# udoo.net
KiCad netlist of a schematic drawn in EAGLE
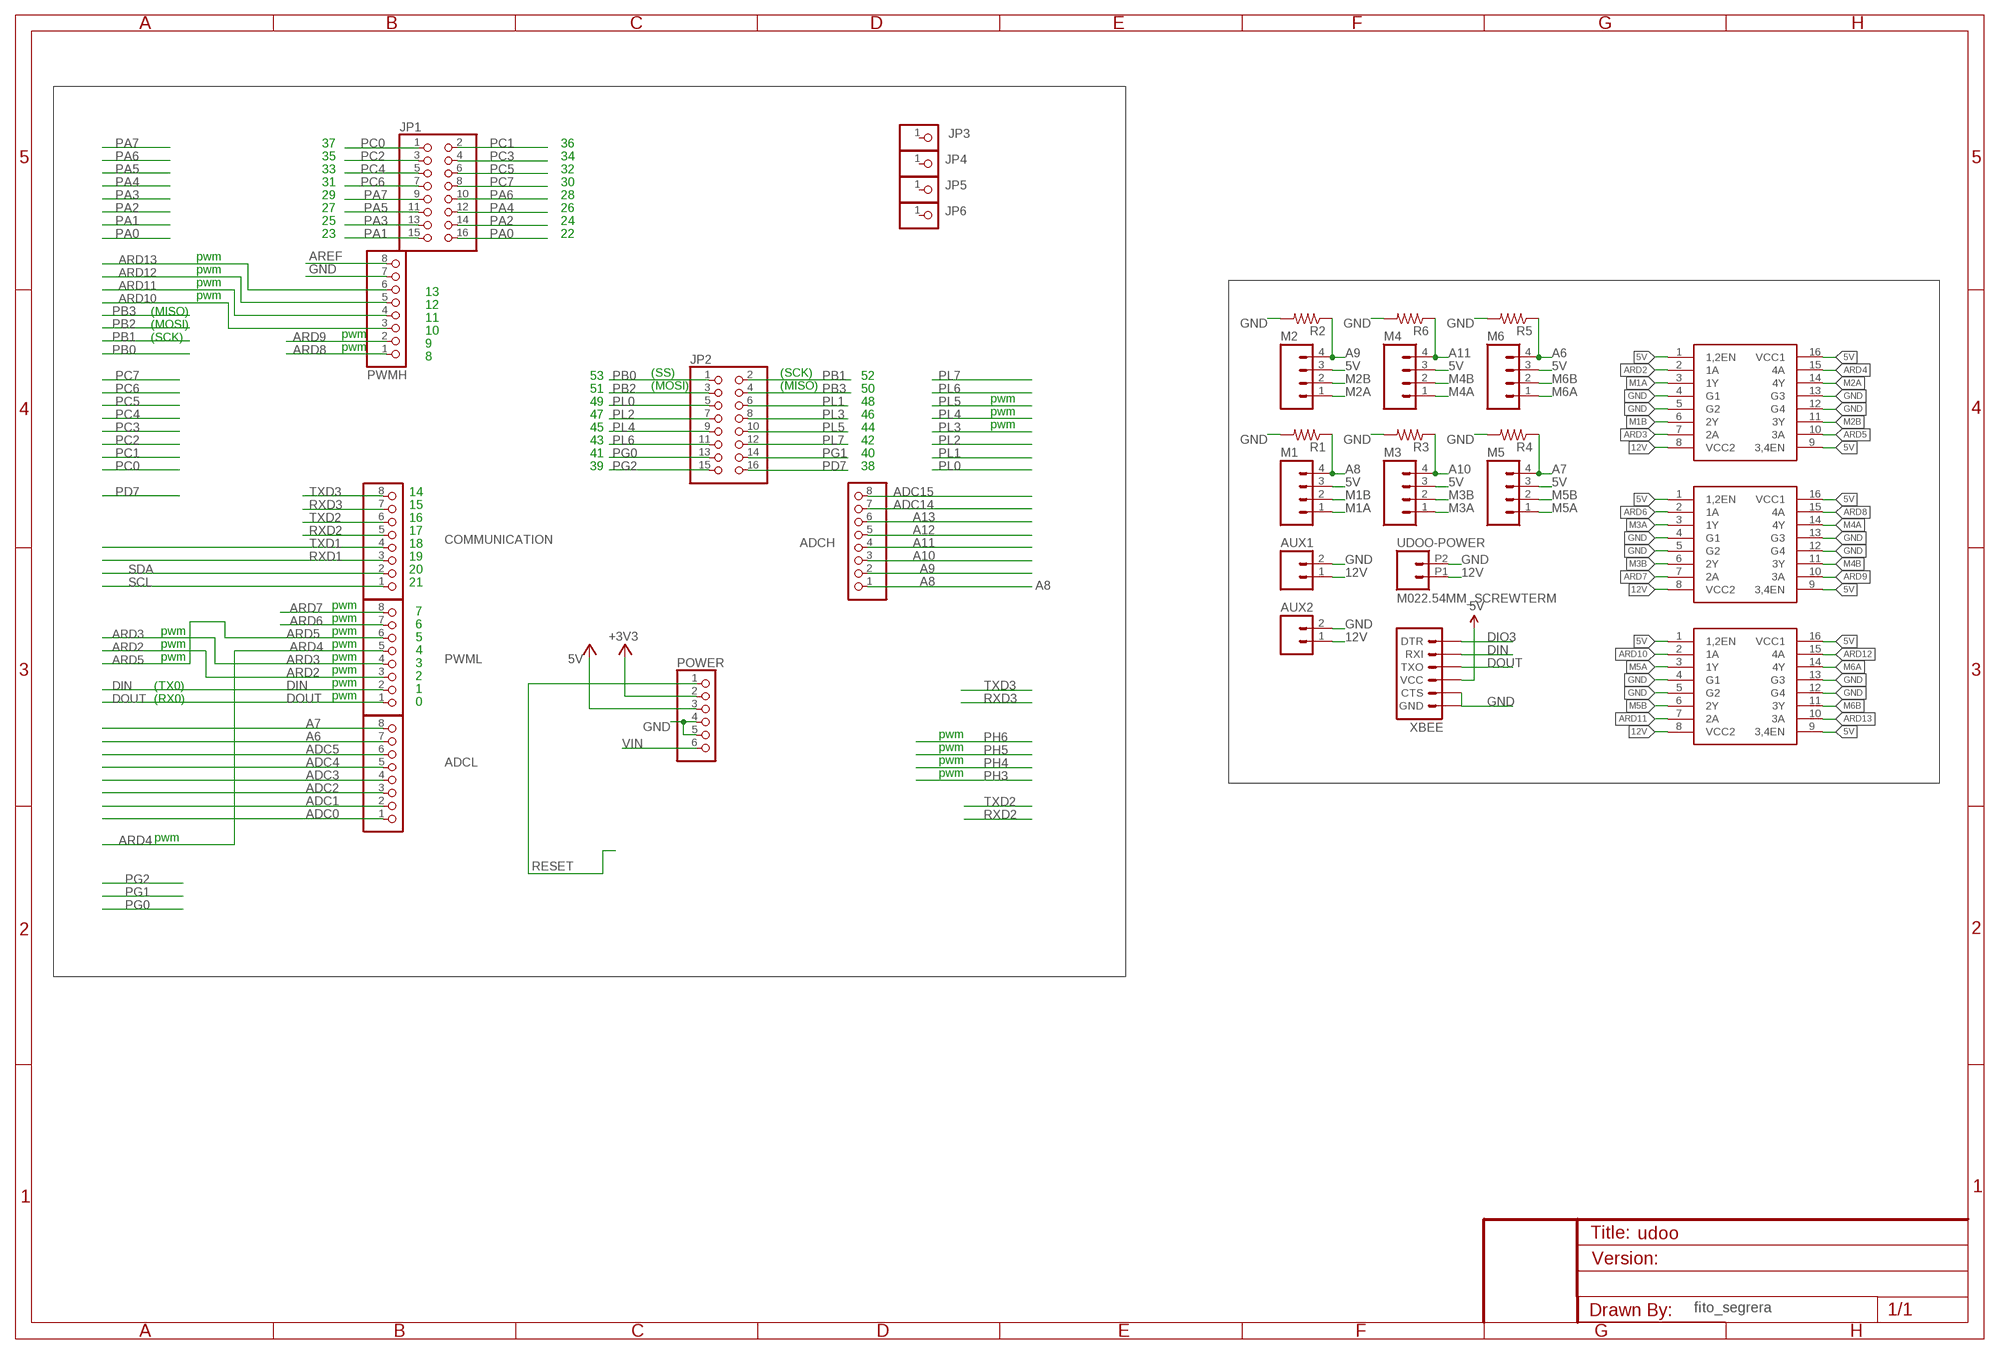
[diagram p0: schematic, sheet 1]

(export (version "E")
  (design (tool "Eeschema 10.0.6"))
  (components
    (comp (ref "ADCH")
      (value "PINHD-1X8")
      (footprint "eagle-import:1X08")
      (libsource (lib "eagle-import") (part "PINHD-1X8"))
    )
    (comp (ref "ADCL")
      (value "PINHD-1X8")
      (footprint "eagle-import:1X08")
      (libsource (lib "eagle-import") (part "PINHD-1X8"))
    )
    (comp (ref "AUX1")
      (value "M02PTH")
      (footprint "eagle-import:1X02")
      (libsource (lib "eagle-import") (part "M02PTH"))
    )
    (comp (ref "AUX2")
      (value "M02PTH")
      (footprint "eagle-import:1X02")
      (libsource (lib "eagle-import") (part "M02PTH"))
    )
    (comp (ref "COMMUNICATION")
      (value "PINHD-1X8")
      (footprint "eagle-import:1X08")
      (libsource (lib "eagle-import") (part "PINHD-1X8"))
    )
    (comp (ref "JP1")
      (value "PINHD-2X8")
      (footprint "eagle-import:2X08")
      (libsource (lib "eagle-import") (part "PINHD-2X8"))
    )
    (comp (ref "JP2")
      (value "PINHD-2X8")
      (footprint "eagle-import:2X08")
      (libsource (lib "eagle-import") (part "PINHD-2X8"))
    )
    (comp (ref "JP3")
      (value "PINHD-1X1")
      (footprint "eagle-import:1X01")
      (libsource (lib "eagle-import") (part "PINHD-1X1"))
    )
    (comp (ref "JP4")
      (value "PINHD-1X1")
      (footprint "eagle-import:1X01")
      (libsource (lib "eagle-import") (part "PINHD-1X1"))
    )
    (comp (ref "JP5")
      (value "PINHD-1X1")
      (footprint "eagle-import:1X01")
      (libsource (lib "eagle-import") (part "PINHD-1X1"))
    )
    (comp (ref "JP6")
      (value "PINHD-1X1")
      (footprint "eagle-import:1X01")
      (libsource (lib "eagle-import") (part "PINHD-1X1"))
    )
    (comp (ref "M1")
      (value "M04JST")
      (footprint "eagle-import:1X04-1.5MM_JST")
      (libsource (lib "eagle-import") (part "M04JST"))
    )
    (comp (ref "M2")
      (value "M04JST")
      (footprint "eagle-import:1X04-1.5MM_JST")
      (libsource (lib "eagle-import") (part "M04JST"))
    )
    (comp (ref "M3")
      (value "M04JST")
      (footprint "eagle-import:1X04-1.5MM_JST")
      (libsource (lib "eagle-import") (part "M04JST"))
    )
    (comp (ref "M4")
      (value "M04JST")
      (footprint "eagle-import:1X04-1.5MM_JST")
      (libsource (lib "eagle-import") (part "M04JST"))
    )
    (comp (ref "M5")
      (value "M04JST")
      (footprint "eagle-import:1X04-1.5MM_JST")
      (libsource (lib "eagle-import") (part "M04JST"))
    )
    (comp (ref "M6")
      (value "M04JST")
      (footprint "eagle-import:1X04-1.5MM_JST")
      (libsource (lib "eagle-import") (part "M04JST"))
    )
    (comp (ref "POWER")
      (value "PINHD-1X6")
      (footprint "eagle-import:1X06")
      (libsource (lib "eagle-import") (part "PINHD-1X6"))
    )
    (comp (ref "PWMH")
      (value "PINHD-1X8")
      (footprint "eagle-import:1X08")
      (libsource (lib "eagle-import") (part "PINHD-1X8"))
    )
    (comp (ref "PWML")
      (value "PINHD-1X8")
      (footprint "eagle-import:1X08")
      (libsource (lib "eagle-import") (part "PINHD-1X8"))
    )
    (comp (ref "R1")
      (value "RESISTOR0805-RES")
      (footprint "eagle-import:0805")
      (libsource (lib "eagle-import") (part "RESISTOR0805-RES"))
    )
    (comp (ref "R2")
      (value "RESISTOR0805-RES")
      (footprint "eagle-import:0805")
      (libsource (lib "eagle-import") (part "RESISTOR0805-RES"))
    )
    (comp (ref "R3")
      (value "RESISTOR0805-RES")
      (footprint "eagle-import:0805")
      (libsource (lib "eagle-import") (part "RESISTOR0805-RES"))
    )
    (comp (ref "R4")
      (value "RESISTOR0805-RES")
      (footprint "eagle-import:0805")
      (libsource (lib "eagle-import") (part "RESISTOR0805-RES"))
    )
    (comp (ref "R5")
      (value "RESISTOR0805-RES")
      (footprint "eagle-import:0805")
      (libsource (lib "eagle-import") (part "RESISTOR0805-RES"))
    )
    (comp (ref "R6")
      (value "RESISTOR0805-RES")
      (footprint "eagle-import:0805")
      (libsource (lib "eagle-import") (part "RESISTOR0805-RES"))
    )
    (comp (ref "U$1")
      (value "HBRIDGE")
      (footprint "eagle-import:HBRIDGE")
      (libsource (lib "eagle-import") (part "HBRIDGE"))
    )
    (comp (ref "U$2")
      (value "HBRIDGE")
      (footprint "eagle-import:HBRIDGE")
      (libsource (lib "eagle-import") (part "HBRIDGE"))
    )
    (comp (ref "U$3")
      (value "HBRIDGE")
      (footprint "eagle-import:HBRIDGE")
      (libsource (lib "eagle-import") (part "HBRIDGE"))
    )
    (comp (ref "UDOO-POWER")
      (value "M022.54MM_SCREWTERM")
      (footprint "eagle-import:1X02_2.54_SCREWTERM")
      (libsource (lib "eagle-import") (part "M022.54MM_SCREWTERM"))
    )
    (comp (ref "XBEE")
      (value "ARDUINO_SERIAL_PROGRAMPTH")
      (footprint "eagle-import:1X06")
      (libsource (lib "eagle-import") (part "ARDUINO_SERIAL_PROGRAMPTH"))
    )
  )
  (nets
    (net (code "1") (name "+3V3") (class "Default")
      (node (ref "POWER") (pin "2") (pinfunction "2_2") (pintype "passive"))
    )
    (net (code "2") (name "/A6") (class "Default")
      (node (ref "ADCL") (pin "7") (pinfunction "7_7") (pintype "passive"))
      (node (ref "M6") (pin "4") (pinfunction "4_4") (pintype "passive"))
      (node (ref "R5") (pin "1") (pinfunction "1_1") (pintype "passive"))
    )
    (net (code "3") (name "/A7") (class "Default")
      (node (ref "ADCL") (pin "8") (pinfunction "8_8") (pintype "passive"))
      (node (ref "M5") (pin "4") (pinfunction "4_4") (pintype "passive"))
      (node (ref "R4") (pin "1") (pinfunction "1_1") (pintype "passive"))
    )
    (net (code "4") (name "/A8") (class "Default")
      (node (ref "ADCH") (pin "1") (pinfunction "1_1") (pintype "passive"))
      (node (ref "M1") (pin "4") (pinfunction "4_4") (pintype "passive"))
      (node (ref "R1") (pin "1") (pinfunction "1_1") (pintype "passive"))
    )
    (net (code "5") (name "/A9") (class "Default")
      (node (ref "ADCH") (pin "2") (pinfunction "2_2") (pintype "passive"))
      (node (ref "M2") (pin "4") (pinfunction "4_4") (pintype "passive"))
      (node (ref "R2") (pin "1") (pinfunction "1_1") (pintype "passive"))
    )
    (net (code "6") (name "/A10") (class "Default")
      (node (ref "ADCH") (pin "3") (pinfunction "3_3") (pintype "passive"))
      (node (ref "M3") (pin "4") (pinfunction "4_4") (pintype "passive"))
      (node (ref "R3") (pin "1") (pinfunction "1_1") (pintype "passive"))
    )
    (net (code "7") (name "/A11") (class "Default")
      (node (ref "ADCH") (pin "4") (pinfunction "4_4") (pintype "passive"))
      (node (ref "M4") (pin "4") (pinfunction "4_4") (pintype "passive"))
      (node (ref "R6") (pin "1") (pinfunction "1_1") (pintype "passive"))
    )
    (net (code "8") (name "/A12") (class "Default")
      (node (ref "ADCH") (pin "5") (pinfunction "5_5") (pintype "passive"))
    )
    (net (code "9") (name "/A13") (class "Default")
      (node (ref "ADCH") (pin "6") (pinfunction "6_6") (pintype "passive"))
    )
    (net (code "10") (name "/ADC0") (class "Default")
      (node (ref "ADCL") (pin "1") (pinfunction "1_1") (pintype "passive"))
    )
    (net (code "11") (name "/ADC1") (class "Default")
      (node (ref "ADCL") (pin "2") (pinfunction "2_2") (pintype "passive"))
    )
    (net (code "12") (name "/ADC2") (class "Default")
      (node (ref "ADCL") (pin "3") (pinfunction "3_3") (pintype "passive"))
    )
    (net (code "13") (name "/ADC3") (class "Default")
      (node (ref "ADCL") (pin "4") (pinfunction "4_4") (pintype "passive"))
    )
    (net (code "14") (name "/ADC4") (class "Default")
      (node (ref "ADCL") (pin "5") (pinfunction "5_5") (pintype "passive"))
    )
    (net (code "15") (name "/ADC5") (class "Default")
      (node (ref "ADCL") (pin "6") (pinfunction "6_6") (pintype "passive"))
    )
    (net (code "16") (name "/ADC14") (class "Default")
      (node (ref "ADCH") (pin "7") (pinfunction "7_7") (pintype "passive"))
    )
    (net (code "17") (name "/ADC15") (class "Default")
      (node (ref "ADCH") (pin "8") (pinfunction "8_8") (pintype "passive"))
    )
    (net (code "18") (name "/AREF") (class "Default")
      (node (ref "PWMH") (pin "8") (pinfunction "8_8") (pintype "passive"))
    )
    (net (code "19") (name "/DIN") (class "Default")
      (node (ref "PWML") (pin "2") (pinfunction "2_2") (pintype "passive"))
      (node (ref "XBEE") (pin "2") (pinfunction "RXI_2") (pintype "passive"))
    )
    (net (code "20") (name "/DIO3") (class "Default")
      (node (ref "XBEE") (pin "1") (pinfunction "DTR_1") (pintype "passive"))
    )
    (net (code "21") (name "/DOUT") (class "Default")
      (node (ref "PWML") (pin "1") (pinfunction "1_1") (pintype "passive"))
      (node (ref "XBEE") (pin "3") (pinfunction "TXO_3") (pintype "passive"))
    )
    (net (code "22") (name "/PA0") (class "Default")
      (node (ref "JP1") (pin "16") (pinfunction "16_16") (pintype "passive"))
    )
    (net (code "23") (name "/PA1") (class "Default")
      (node (ref "JP1") (pin "15") (pinfunction "15_15") (pintype "passive"))
    )
    (net (code "24") (name "/PA2") (class "Default")
      (node (ref "JP1") (pin "14") (pinfunction "14_14") (pintype "passive"))
    )
    (net (code "25") (name "/PA3") (class "Default")
      (node (ref "JP1") (pin "13") (pinfunction "13_13") (pintype "passive"))
    )
    (net (code "26") (name "/PA4") (class "Default")
      (node (ref "JP1") (pin "12") (pinfunction "12_12") (pintype "passive"))
    )
    (net (code "27") (name "/PA5") (class "Default")
      (node (ref "JP1") (pin "11") (pinfunction "11_11") (pintype "passive"))
    )
    (net (code "28") (name "/PA6") (class "Default")
      (node (ref "JP1") (pin "10") (pinfunction "10_10") (pintype "passive"))
    )
    (net (code "29") (name "/PA7") (class "Default")
      (node (ref "JP1") (pin "9") (pinfunction "9_9") (pintype "passive"))
    )
    (net (code "30") (name "/PB0") (class "Default")
      (node (ref "JP2") (pin "1") (pinfunction "1_1") (pintype "passive"))
    )
    (net (code "31") (name "/PB1") (class "Default")
      (node (ref "JP2") (pin "2") (pinfunction "2_2") (pintype "passive"))
    )
    (net (code "32") (name "/PB2") (class "Default")
      (node (ref "JP2") (pin "3") (pinfunction "3_3") (pintype "passive"))
    )
    (net (code "33") (name "/PB3") (class "Default")
      (node (ref "JP2") (pin "4") (pinfunction "4_4") (pintype "passive"))
    )
    (net (code "34") (name "/PC0") (class "Default")
      (node (ref "JP1") (pin "1") (pinfunction "1_1") (pintype "passive"))
    )
    (net (code "35") (name "/PC1") (class "Default")
      (node (ref "JP1") (pin "2") (pinfunction "2_2") (pintype "passive"))
    )
    (net (code "36") (name "/PC2") (class "Default")
      (node (ref "JP1") (pin "3") (pinfunction "3_3") (pintype "passive"))
    )
    (net (code "37") (name "/PC3") (class "Default")
      (node (ref "JP1") (pin "4") (pinfunction "4_4") (pintype "passive"))
    )
    (net (code "38") (name "/PC4") (class "Default")
      (node (ref "JP1") (pin "5") (pinfunction "5_5") (pintype "passive"))
    )
    (net (code "39") (name "/PC5") (class "Default")
      (node (ref "JP1") (pin "6") (pinfunction "6_6") (pintype "passive"))
    )
    (net (code "40") (name "/PC6") (class "Default")
      (node (ref "JP1") (pin "7") (pinfunction "7_7") (pintype "passive"))
    )
    (net (code "41") (name "/PC7") (class "Default")
      (node (ref "JP1") (pin "8") (pinfunction "8_8") (pintype "passive"))
    )
    (net (code "42") (name "/PD7") (class "Default")
      (node (ref "JP2") (pin "16") (pinfunction "16_16") (pintype "passive"))
    )
    (net (code "43") (name "/PG0") (class "Default")
      (node (ref "JP2") (pin "13") (pinfunction "13_13") (pintype "passive"))
    )
    (net (code "44") (name "/PG1") (class "Default")
      (node (ref "JP2") (pin "14") (pinfunction "14_14") (pintype "passive"))
    )
    (net (code "45") (name "/PG2") (class "Default")
      (node (ref "JP2") (pin "15") (pinfunction "15_15") (pintype "passive"))
    )
    (net (code "50") (name "/PL0") (class "Default")
      (node (ref "JP2") (pin "5") (pinfunction "5_5") (pintype "passive"))
    )
    (net (code "51") (name "/PL1") (class "Default")
      (node (ref "JP2") (pin "6") (pinfunction "6_6") (pintype "passive"))
    )
    (net (code "52") (name "/PL2") (class "Default")
      (node (ref "JP2") (pin "7") (pinfunction "7_7") (pintype "passive"))
    )
    (net (code "53") (name "/PL3") (class "Default")
      (node (ref "JP2") (pin "8") (pinfunction "8_8") (pintype "passive"))
    )
    (net (code "54") (name "/PL4") (class "Default")
      (node (ref "JP2") (pin "9") (pinfunction "9_9") (pintype "passive"))
    )
    (net (code "55") (name "/PL5") (class "Default")
      (node (ref "JP2") (pin "10") (pinfunction "10_10") (pintype "passive"))
    )
    (net (code "56") (name "/PL6") (class "Default")
      (node (ref "JP2") (pin "11") (pinfunction "11_11") (pintype "passive"))
    )
    (net (code "57") (name "/PL7") (class "Default")
      (node (ref "JP2") (pin "12") (pinfunction "12_12") (pintype "passive"))
    )
    (net (code "58") (name "/RESET") (class "Default")
      (node (ref "POWER") (pin "1") (pinfunction "1_1") (pintype "passive"))
    )
    (net (code "59") (name "/RXD1") (class "Default")
      (node (ref "COMMUNICATION") (pin "3") (pinfunction "3_3") (pintype "passive"))
    )
    (net (code "60") (name "/RXD2") (class "Default")
      (node (ref "COMMUNICATION") (pin "5") (pinfunction "5_5") (pintype "passive"))
    )
    (net (code "61") (name "/RXD3") (class "Default")
      (node (ref "COMMUNICATION") (pin "7") (pinfunction "7_7") (pintype "passive"))
    )
    (net (code "62") (name "/SCL") (class "Default")
      (node (ref "COMMUNICATION") (pin "1") (pinfunction "1_1") (pintype "passive"))
    )
    (net (code "63") (name "/SDA") (class "Default")
      (node (ref "COMMUNICATION") (pin "2") (pinfunction "2_2") (pintype "passive"))
    )
    (net (code "64") (name "/TXD1") (class "Default")
      (node (ref "COMMUNICATION") (pin "4") (pinfunction "4_4") (pintype "passive"))
    )
    (net (code "65") (name "/TXD2") (class "Default")
      (node (ref "COMMUNICATION") (pin "6") (pinfunction "6_6") (pintype "passive"))
    )
    (net (code "66") (name "/TXD3") (class "Default")
      (node (ref "COMMUNICATION") (pin "8") (pinfunction "8_8") (pintype "passive"))
    )
    (net (code "67") (name "/VIN") (class "Default")
      (node (ref "POWER") (pin "6") (pinfunction "6_6") (pintype "passive"))
    )
    (net (code "68") (name "5V") (class "Default")
      (node (ref "M1") (pin "3") (pinfunction "3_3") (pintype "passive"))
      (node (ref "M2") (pin "3") (pinfunction "3_3") (pintype "passive"))
      (node (ref "M3") (pin "3") (pinfunction "3_3") (pintype "passive"))
      (node (ref "M4") (pin "3") (pinfunction "3_3") (pintype "passive"))
      (node (ref "M5") (pin "3") (pinfunction "3_3") (pintype "passive"))
      (node (ref "M6") (pin "3") (pinfunction "3_3") (pintype "passive"))
      (node (ref "POWER") (pin "3") (pinfunction "3_3") (pintype "passive"))
      (node (ref "U$1") (pin "1") (pinfunction "1,2EN_1") (pintype "bidirectional"))
      (node (ref "U$1") (pin "16") (pinfunction "VCC1_16") (pintype "bidirectional"))
      (node (ref "U$1") (pin "9") (pinfunction "3,4EN_9") (pintype "bidirectional"))
      (node (ref "U$2") (pin "1") (pinfunction "1,2EN_1") (pintype "bidirectional"))
      (node (ref "U$2") (pin "16") (pinfunction "VCC1_16") (pintype "bidirectional"))
      (node (ref "U$2") (pin "9") (pinfunction "3,4EN_9") (pintype "bidirectional"))
      (node (ref "U$3") (pin "1") (pinfunction "1,2EN_1") (pintype "bidirectional"))
      (node (ref "U$3") (pin "16") (pinfunction "VCC1_16") (pintype "bidirectional"))
      (node (ref "U$3") (pin "9") (pinfunction "3,4EN_9") (pintype "bidirectional"))
      (node (ref "XBEE") (pin "4") (pinfunction "VCC_4") (pintype "passive"))
    )
    (net (code "69") (name "12V") (class "Default")
      (node (ref "AUX1") (pin "1") (pinfunction "1_1") (pintype "passive"))
      (node (ref "AUX2") (pin "1") (pinfunction "1_1") (pintype "passive"))
      (node (ref "U$1") (pin "8") (pinfunction "VCC2_8") (pintype "bidirectional"))
      (node (ref "U$2") (pin "8") (pinfunction "VCC2_8") (pintype "bidirectional"))
      (node (ref "U$3") (pin "8") (pinfunction "VCC2_8") (pintype "bidirectional"))
      (node (ref "UDOO-POWER") (pin "P1") (pinfunction "1_P1") (pintype "passive"))
    )
    (net (code "70") (name "ARD2") (class "Default")
      (node (ref "PWML") (pin "3") (pinfunction "3_3") (pintype "passive"))
      (node (ref "U$1") (pin "2") (pinfunction "1A_2") (pintype "bidirectional"))
    )
    (net (code "71") (name "ARD3") (class "Default")
      (node (ref "PWML") (pin "4") (pinfunction "4_4") (pintype "passive"))
      (node (ref "U$1") (pin "7") (pinfunction "2A_7") (pintype "bidirectional"))
    )
    (net (code "72") (name "ARD4") (class "Default")
      (node (ref "PWML") (pin "5") (pinfunction "5_5") (pintype "passive"))
      (node (ref "U$1") (pin "15") (pinfunction "4A_15") (pintype "bidirectional"))
    )
    (net (code "73") (name "ARD5") (class "Default")
      (node (ref "PWML") (pin "6") (pinfunction "6_6") (pintype "passive"))
      (node (ref "U$1") (pin "10") (pinfunction "3A_10") (pintype "bidirectional"))
    )
    (net (code "74") (name "ARD6") (class "Default")
      (node (ref "PWML") (pin "7") (pinfunction "7_7") (pintype "passive"))
      (node (ref "U$2") (pin "2") (pinfunction "1A_2") (pintype "bidirectional"))
    )
    (net (code "75") (name "ARD7") (class "Default")
      (node (ref "PWML") (pin "8") (pinfunction "8_8") (pintype "passive"))
      (node (ref "U$2") (pin "7") (pinfunction "2A_7") (pintype "bidirectional"))
    )
    (net (code "76") (name "ARD8") (class "Default")
      (node (ref "PWMH") (pin "1") (pinfunction "1_1") (pintype "passive"))
      (node (ref "U$2") (pin "15") (pinfunction "4A_15") (pintype "bidirectional"))
    )
    (net (code "77") (name "ARD9") (class "Default")
      (node (ref "PWMH") (pin "2") (pinfunction "2_2") (pintype "passive"))
      (node (ref "U$2") (pin "10") (pinfunction "3A_10") (pintype "bidirectional"))
    )
    (net (code "78") (name "ARD10") (class "Default")
      (node (ref "PWMH") (pin "3") (pinfunction "3_3") (pintype "passive"))
      (node (ref "U$3") (pin "2") (pinfunction "1A_2") (pintype "bidirectional"))
    )
    (net (code "79") (name "ARD11") (class "Default")
      (node (ref "PWMH") (pin "4") (pinfunction "4_4") (pintype "passive"))
      (node (ref "U$3") (pin "7") (pinfunction "2A_7") (pintype "bidirectional"))
    )
    (net (code "80") (name "ARD12") (class "Default")
      (node (ref "PWMH") (pin "5") (pinfunction "5_5") (pintype "passive"))
      (node (ref "U$3") (pin "15") (pinfunction "4A_15") (pintype "bidirectional"))
    )
    (net (code "81") (name "ARD13") (class "Default")
      (node (ref "PWMH") (pin "6") (pinfunction "6_6") (pintype "passive"))
      (node (ref "U$3") (pin "10") (pinfunction "3A_10") (pintype "bidirectional"))
    )
    (net (code "82") (name "GND") (class "Default")
      (node (ref "AUX1") (pin "2") (pinfunction "2_2") (pintype "passive"))
      (node (ref "AUX2") (pin "2") (pinfunction "2_2") (pintype "passive"))
      (node (ref "POWER") (pin "4") (pinfunction "4_4") (pintype "passive"))
      (node (ref "POWER") (pin "5") (pinfunction "5_5") (pintype "passive"))
      (node (ref "PWMH") (pin "7") (pinfunction "7_7") (pintype "passive"))
      (node (ref "R1") (pin "2") (pinfunction "2_2") (pintype "passive"))
      (node (ref "R2") (pin "2") (pinfunction "2_2") (pintype "passive"))
      (node (ref "R3") (pin "2") (pinfunction "2_2") (pintype "passive"))
      (node (ref "R4") (pin "2") (pinfunction "2_2") (pintype "passive"))
      (node (ref "R5") (pin "2") (pinfunction "2_2") (pintype "passive"))
      (node (ref "R6") (pin "2") (pinfunction "2_2") (pintype "passive"))
      (node (ref "U$1") (pin "12") (pinfunction "G4_12") (pintype "bidirectional"))
      (node (ref "U$1") (pin "13") (pinfunction "G3_13") (pintype "bidirectional"))
      (node (ref "U$1") (pin "4") (pinfunction "G1_4") (pintype "bidirectional"))
      (node (ref "U$1") (pin "5") (pinfunction "G2_5") (pintype "bidirectional"))
      (node (ref "U$2") (pin "12") (pinfunction "G4_12") (pintype "bidirectional"))
      (node (ref "U$2") (pin "13") (pinfunction "G3_13") (pintype "bidirectional"))
      (node (ref "U$2") (pin "4") (pinfunction "G1_4") (pintype "bidirectional"))
      (node (ref "U$2") (pin "5") (pinfunction "G2_5") (pintype "bidirectional"))
      (node (ref "U$3") (pin "12") (pinfunction "G4_12") (pintype "bidirectional"))
      (node (ref "U$3") (pin "13") (pinfunction "G3_13") (pintype "bidirectional"))
      (node (ref "U$3") (pin "4") (pinfunction "G1_4") (pintype "bidirectional"))
      (node (ref "U$3") (pin "5") (pinfunction "G2_5") (pintype "bidirectional"))
      (node (ref "UDOO-POWER") (pin "P2") (pinfunction "2_P2") (pintype "passive"))
      (node (ref "XBEE") (pin "5") (pinfunction "CTS_5") (pintype "passive"))
      (node (ref "XBEE") (pin "6") (pinfunction "GND_6") (pintype "passive"))
    )
    (net (code "83") (name "M1A") (class "Default")
      (node (ref "M1") (pin "1") (pinfunction "1_1") (pintype "passive"))
      (node (ref "U$1") (pin "3") (pinfunction "1Y_3") (pintype "bidirectional"))
    )
    (net (code "84") (name "M1B") (class "Default")
      (node (ref "M1") (pin "2") (pinfunction "2_2") (pintype "passive"))
      (node (ref "U$1") (pin "6") (pinfunction "2Y_6") (pintype "bidirectional"))
    )
    (net (code "85") (name "M2A") (class "Default")
      (node (ref "M2") (pin "1") (pinfunction "1_1") (pintype "passive"))
      (node (ref "U$1") (pin "14") (pinfunction "4Y_14") (pintype "bidirectional"))
    )
    (net (code "86") (name "M2B") (class "Default")
      (node (ref "M2") (pin "2") (pinfunction "2_2") (pintype "passive"))
      (node (ref "U$1") (pin "11") (pinfunction "3Y_11") (pintype "bidirectional"))
    )
    (net (code "87") (name "M3A") (class "Default")
      (node (ref "M3") (pin "1") (pinfunction "1_1") (pintype "passive"))
      (node (ref "U$2") (pin "3") (pinfunction "1Y_3") (pintype "bidirectional"))
    )
    (net (code "88") (name "M3B") (class "Default")
      (node (ref "M3") (pin "2") (pinfunction "2_2") (pintype "passive"))
      (node (ref "U$2") (pin "6") (pinfunction "2Y_6") (pintype "bidirectional"))
    )
    (net (code "89") (name "M4A") (class "Default")
      (node (ref "M4") (pin "1") (pinfunction "1_1") (pintype "passive"))
      (node (ref "U$2") (pin "14") (pinfunction "4Y_14") (pintype "bidirectional"))
    )
    (net (code "90") (name "M4B") (class "Default")
      (node (ref "M4") (pin "2") (pinfunction "2_2") (pintype "passive"))
      (node (ref "U$2") (pin "11") (pinfunction "3Y_11") (pintype "bidirectional"))
    )
    (net (code "91") (name "M5A") (class "Default")
      (node (ref "M5") (pin "1") (pinfunction "1_1") (pintype "passive"))
      (node (ref "U$3") (pin "3") (pinfunction "1Y_3") (pintype "bidirectional"))
    )
    (net (code "92") (name "M5B") (class "Default")
      (node (ref "M5") (pin "2") (pinfunction "2_2") (pintype "passive"))
      (node (ref "U$3") (pin "6") (pinfunction "2Y_6") (pintype "bidirectional"))
    )
    (net (code "93") (name "M6A") (class "Default")
      (node (ref "M6") (pin "1") (pinfunction "1_1") (pintype "passive"))
      (node (ref "U$3") (pin "14") (pinfunction "4Y_14") (pintype "bidirectional"))
    )
    (net (code "94") (name "M6B") (class "Default")
      (node (ref "M6") (pin "2") (pinfunction "2_2") (pintype "passive"))
      (node (ref "U$3") (pin "11") (pinfunction "3Y_11") (pintype "bidirectional"))
    )
    (net (code "95") (name "unconnected-(JP3-Pad1)") (class "Default")
      (node (ref "JP3") (pin "1") (pinfunction "1_1") (pintype "passive"))
    )
    (net (code "96") (name "unconnected-(JP4-Pad1)") (class "Default")
      (node (ref "JP4") (pin "1") (pinfunction "1_1") (pintype "passive"))
    )
    (net (code "97") (name "unconnected-(JP5-Pad1)") (class "Default")
      (node (ref "JP5") (pin "1") (pinfunction "1_1") (pintype "passive"))
    )
    (net (code "98") (name "unconnected-(JP6-Pad1)") (class "Default")
      (node (ref "JP6") (pin "1") (pinfunction "1_1") (pintype "passive"))
    )
  )
)
